# ESC.net
KiCad netlist of a schematic drawn in Altium Designer
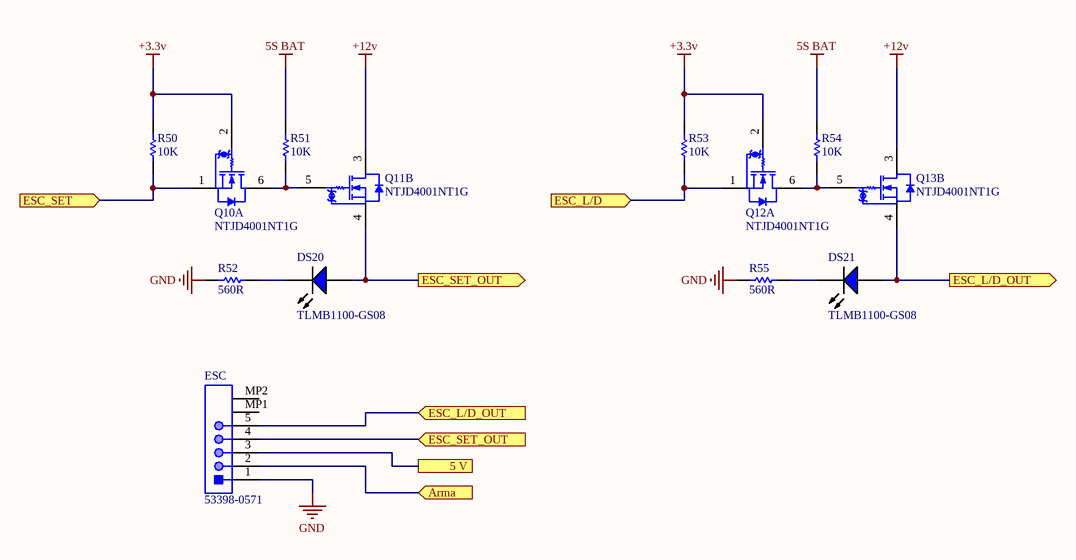
[diagram p0: ESC.SchDoc]

(export (version "E")
  (design (tool "Eeschema 10.0.6"))
  (components
    (comp (ref "DS20")
      (value "TLMB1100-GS08")
      (footprint "VISH-TLMX1100-2_V")
      (fields (field (name "TOLERANCE") "10%"))
      (libsource (lib "Altium Content Vault") (part "CMP-1666-00028-1"))
    )
    (comp (ref "DS21")
      (value "TLMB1100-GS08")
      (footprint "VISH-TLMX1100-2_V")
      (fields (field (name "TOLERANCE") "10%"))
      (libsource (lib "Altium Content Vault") (part "CMP-1666-00028-1"))
    )
    (comp (ref "ESC")
      (value "53398-0571")
      (footprint "MOLX-53398-0571-5_V")
      (fields (field (name "MANUFACTURER") "Molex"))
      (libsource (lib "Moles_53398-0571") (part "CMP-2000-05250-1"))
    )
    (comp (ref "Q10")
      (value "NTJD4001NT1G")
      (footprint "ONSC-SOT-363-6-419B-02_W_V")
      (fields (field (name "MANUFACTURER") "On Semiconductor"))
      (libsource (lib "Altium Content Vault") (part "ONSC-NNMOS-6_D"))
    )
    (comp (ref "Q11")
      (value "NTJD4001NT1G")
      (footprint "ONSC-SOT-363-6-419B-02_W_V")
      (fields (field (name "MANUFACTURER") "On Semiconductor"))
      (libsource (lib "Altium Content Vault") (part "ONSC-NNMOS-6_D"))
    )
    (comp (ref "Q12")
      (value "NTJD4001NT1G")
      (footprint "ONSC-SOT-363-6-419B-02_W_V")
      (fields (field (name "MANUFACTURER") "On Semiconductor"))
      (libsource (lib "Altium Content Vault") (part "ONSC-NNMOS-6_D"))
    )
    (comp (ref "Q13")
      (value "NTJD4001NT1G")
      (footprint "ONSC-SOT-363-6-419B-02_W_V")
      (fields (field (name "MANUFACTURER") "On Semiconductor"))
      (libsource (lib "Altium Content Vault") (part "ONSC-NNMOS-6_D"))
    )
    (comp (ref "R50")
      (value "10K")
      (footprint "RES-0402")
      (fields (field (name "Comment") "CRCW040210K0FKEDC"))
      (libsource (lib "Schlib1") (part "RES 1K 0402"))
    )
    (comp (ref "R51")
      (value "10K")
      (footprint "RES-0402")
      (fields (field (name "Comment") "CRCW040210K0FKEDC"))
      (libsource (lib "Schlib1") (part "RES 1K 0402"))
    )
    (comp (ref "R52")
      (value "560R")
      (footprint "RES-0402")
      (fields (field (name "Comment") "RR0510P-561-D"))
      (libsource (lib "Schlib1") (part "RES 1K 0402"))
    )
    (comp (ref "R53")
      (value "10K")
      (footprint "RES-0402")
      (fields (field (name "Comment") "CRCW040210K0FKEDC"))
      (libsource (lib "Schlib1") (part "RES 1K 0402"))
    )
    (comp (ref "R54")
      (value "10K")
      (footprint "RES-0402")
      (fields (field (name "Comment") "CRCW040210K0FKEDC"))
      (libsource (lib "Schlib1") (part "RES 1K 0402"))
    )
    (comp (ref "R55")
      (value "560R")
      (footprint "RES-0402")
      (fields (field (name "Comment") "RR0510P-561-D"))
      (libsource (lib "Schlib1") (part "RES 1K 0402"))
    )
  )
  (nets
    (net (code "1") (name "+3.3v") (class "Default")
      (node (ref "Q10") (pin "2") (pinfunction "G1_2") (pintype "passive"))
      (node (ref "Q12") (pin "2") (pinfunction "G1_2") (pintype "passive"))
      (node (ref "R50") (pin "2") (pinfunction "2_2") (pintype "passive"))
      (node (ref "R53") (pin "2") (pinfunction "2_2") (pintype "passive"))
    )
    (net (code "2") (name "+12v") (class "Default")
      (node (ref "Q11") (pin "3") (pinfunction "D2_3") (pintype "passive"))
      (node (ref "Q13") (pin "3") (pinfunction "D2_3") (pintype "passive"))
    )
    (net (code "3") (name "/5 V") (class "Default")
      (node (ref "ESC") (pin "3") (pinfunction "3_3") (pintype "passive"))
    )
    (net (code "4") (name "/Arma") (class "Default")
      (node (ref "ESC") (pin "2") (pinfunction "2_2") (pintype "passive"))
    )
    (net (code "5") (name "/ESC_L{slash}D") (class "Default")
      (node (ref "Q12") (pin "1") (pinfunction "S1_1") (pintype "passive"))
      (node (ref "R53") (pin "1") (pinfunction "1_1") (pintype "passive"))
    )
    (net (code "6") (name "/ESC_L{slash}D_OUT") (class "Default")
      (node (ref "DS21") (pin "1") (pinfunction "A_1") (pintype "passive"))
      (node (ref "ESC") (pin "5") (pinfunction "5_5") (pintype "passive"))
      (node (ref "Q13") (pin "4") (pinfunction "S2_4") (pintype "passive"))
    )
    (net (code "7") (name "/ESC_SET") (class "Default")
      (node (ref "Q10") (pin "1") (pinfunction "S1_1") (pintype "passive"))
      (node (ref "R50") (pin "1") (pinfunction "1_1") (pintype "passive"))
    )
    (net (code "8") (name "/ESC_SET_OUT") (class "Default")
      (node (ref "DS20") (pin "1") (pinfunction "A_1") (pintype "passive"))
      (node (ref "ESC") (pin "4") (pinfunction "4_4") (pintype "passive"))
      (node (ref "Q11") (pin "4") (pinfunction "S2_4") (pintype "passive"))
    )
    (net (code "9") (name "5S BAT") (class "Default")
      (node (ref "R51") (pin "2") (pinfunction "2_2") (pintype "passive"))
      (node (ref "R54") (pin "2") (pinfunction "2_2") (pintype "passive"))
    )
    (net (code "10") (name "GND") (class "Default")
      (node (ref "ESC") (pin "1") (pinfunction "1_1") (pintype "passive"))
      (node (ref "R52") (pin "1") (pinfunction "1_1") (pintype "passive"))
      (node (ref "R55") (pin "1") (pinfunction "1_1") (pintype "passive"))
    )
    (net (code "11") (name "Net-(DS20-K)") (class "Default")
      (node (ref "DS20") (pin "2") (pinfunction "K_2") (pintype "passive"))
      (node (ref "R52") (pin "2") (pinfunction "2_2") (pintype "passive"))
    )
    (net (code "12") (name "Net-(DS21-K)") (class "Default")
      (node (ref "DS21") (pin "2") (pinfunction "K_2") (pintype "passive"))
      (node (ref "R55") (pin "2") (pinfunction "2_2") (pintype "passive"))
    )
    (net (code "13") (name "Net-(Q10A-D1)") (class "Default")
      (node (ref "Q10") (pin "6") (pinfunction "D1_6") (pintype "passive"))
      (node (ref "Q11") (pin "5") (pinfunction "G2_5") (pintype "passive"))
      (node (ref "R51") (pin "1") (pinfunction "1_1") (pintype "passive"))
    )
    (net (code "14") (name "Net-(Q12A-D1)") (class "Default")
      (node (ref "Q12") (pin "6") (pinfunction "D1_6") (pintype "passive"))
      (node (ref "Q13") (pin "5") (pinfunction "G2_5") (pintype "passive"))
      (node (ref "R54") (pin "1") (pinfunction "1_1") (pintype "passive"))
    )
    (net (code "15") (name "unconnected-(ESC-PadMP1)") (class "Default")
      (node (ref "ESC") (pin "MP1") (pinfunction "MP1_MP1") (pintype "passive"))
    )
    (net (code "16") (name "unconnected-(ESC-PadMP2)") (class "Default")
      (node (ref "ESC") (pin "MP2") (pinfunction "MP2_MP2") (pintype "passive"))
    )
  )
)
